# ttab.net
KiCad netlist of a schematic drawn in EAGLE
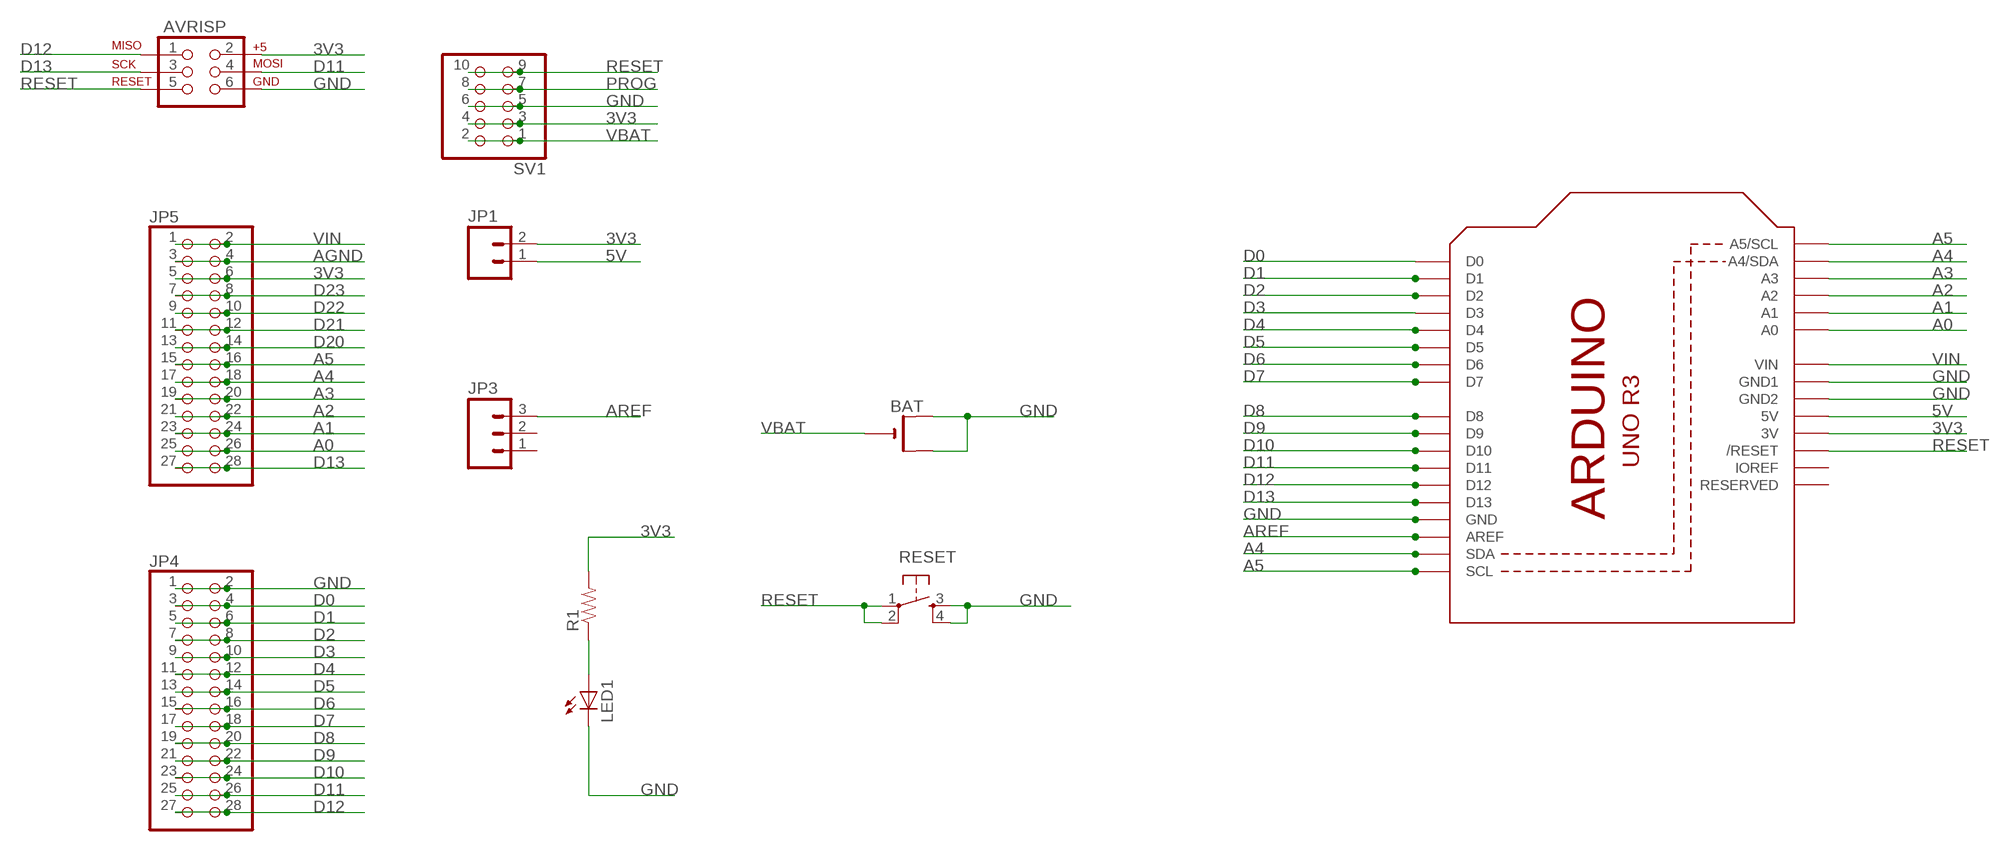
[diagram p0: schematic, sheet 1]

(export (version "E")
  (design (tool "Eeschema 10.0.6"))
  (components
    (comp (ref "AVRISP")
      (value "AVR_SPI_PRG_6PTH")
      (footprint "eagle-import:2X3")
      (libsource (lib "eagle-import") (part "AVR_SPI_PRG_6PTH"))
    )
    (comp (ref "BAT")
      (value "CR1220THM")
      (footprint "eagle-import:CR1220-THM")
      (libsource (lib "eagle-import") (part "CR1220THM"))
    )
    (comp (ref "JP1")
      (value "M02LOCK")
      (footprint "eagle-import:1X02_LOCK")
      (libsource (lib "eagle-import") (part "M02LOCK"))
    )
    (comp (ref "JP3")
      (value "M03PTH")
      (footprint "eagle-import:1X03")
      (libsource (lib "eagle-import") (part "M03PTH"))
    )
    (comp (ref "JP4")
      (value "PINHD-2X14")
      (footprint "eagle-import:2X14")
      (libsource (lib "eagle-import") (part "PINHD-2X14"))
    )
    (comp (ref "JP5")
      (value "PINHD-2X14")
      (footprint "eagle-import:2X14")
      (libsource (lib "eagle-import") (part "PINHD-2X14"))
    )
    (comp (ref "LED1")
      (value "LEDCHIP-LED0805")
      (footprint "eagle-import:CHIP-LED0805")
      (libsource (lib "eagle-import") (part "LEDCHIP-LED0805"))
    )
    (comp (ref "R1")
      (value "RESISTOR0805-RES")
      (footprint "eagle-import:0805")
      (libsource (lib "eagle-import") (part "RESISTOR0805-RES"))
    )
    (comp (ref "RESET")
      (value "TAC_SWITCHPTH")
      (footprint "eagle-import:TACTILE-PTH")
      (libsource (lib "eagle-import") (part "TAC_SWITCHPTH"))
    )
    (comp (ref "SV1")
      (value "PINHD-2X5")
      (footprint "eagle-import:2X05")
      (libsource (lib "eagle-import") (part "PINHD-2X5"))
    )
    (comp (ref "U4")
      (value "ARDUINOR3-DIMENSION")
      (footprint "eagle-import:ARDUINOR3")
      (libsource (lib "eagle-import") (part "ARDUINOR3-DIMENSION"))
    )
  )
  (nets
    (net (code "1") (name "/3V3") (class "Default")
      (node (ref "AVRISP") (pin "2") (pinfunction "2_2") (pintype "passive"))
      (node (ref "JP1") (pin "2") (pinfunction "2_2") (pintype "passive"))
      (node (ref "JP5") (pin "5") (pinfunction "5_5") (pintype "passive"))
      (node (ref "JP5") (pin "6") (pinfunction "6_6") (pintype "passive"))
      (node (ref "R1") (pin "2") (pinfunction "2_2") (pintype "passive"))
      (node (ref "SV1") (pin "3") (pinfunction "3_3") (pintype "passive"))
      (node (ref "SV1") (pin "4") (pinfunction "4_4") (pintype "passive"))
      (node (ref "U4") (pin "3V") (pinfunction "3V_3V") (pintype "power_in"))
    )
    (net (code "2") (name "/5V") (class "Default")
      (node (ref "JP1") (pin "1") (pinfunction "1_1") (pintype "passive"))
      (node (ref "U4") (pin "5V") (pinfunction "5V_5V") (pintype "power_in"))
    )
    (net (code "3") (name "/A0") (class "Default")
      (node (ref "JP5") (pin "25") (pinfunction "25_25") (pintype "passive"))
      (node (ref "JP5") (pin "26") (pinfunction "26_26") (pintype "passive"))
      (node (ref "U4") (pin "A0") (pinfunction "A0_A0") (pintype "bidirectional"))
    )
    (net (code "4") (name "/A1") (class "Default")
      (node (ref "JP5") (pin "23") (pinfunction "23_23") (pintype "passive"))
      (node (ref "JP5") (pin "24") (pinfunction "24_24") (pintype "passive"))
      (node (ref "U4") (pin "A1") (pinfunction "A1_A1") (pintype "bidirectional"))
    )
    (net (code "5") (name "/A2") (class "Default")
      (node (ref "JP5") (pin "21") (pinfunction "21_21") (pintype "passive"))
      (node (ref "JP5") (pin "22") (pinfunction "22_22") (pintype "passive"))
      (node (ref "U4") (pin "A2") (pinfunction "A2_A2") (pintype "bidirectional"))
    )
    (net (code "6") (name "/A3") (class "Default")
      (node (ref "JP5") (pin "19") (pinfunction "19_19") (pintype "passive"))
      (node (ref "JP5") (pin "20") (pinfunction "20_20") (pintype "passive"))
      (node (ref "U4") (pin "A3") (pinfunction "A3_A3") (pintype "bidirectional"))
    )
    (net (code "7") (name "/A4") (class "Default")
      (node (ref "JP5") (pin "17") (pinfunction "17_17") (pintype "passive"))
      (node (ref "JP5") (pin "18") (pinfunction "18_18") (pintype "passive"))
      (node (ref "U4") (pin "A4") (pinfunction "A4/SDA_A4") (pintype "bidirectional"))
      (node (ref "U4") (pin "SDA") (pinfunction "SDA_SDA") (pintype "bidirectional"))
    )
    (net (code "8") (name "/A5") (class "Default")
      (node (ref "JP5") (pin "15") (pinfunction "15_15") (pintype "passive"))
      (node (ref "JP5") (pin "16") (pinfunction "16_16") (pintype "passive"))
      (node (ref "U4") (pin "A5") (pinfunction "A5/SCL_A5") (pintype "bidirectional"))
      (node (ref "U4") (pin "SCL") (pinfunction "SCL_SCL") (pintype "bidirectional"))
    )
    (net (code "9") (name "/AGND") (class "Default")
      (node (ref "JP5") (pin "3") (pinfunction "3_3") (pintype "passive"))
      (node (ref "JP5") (pin "4") (pinfunction "4_4") (pintype "passive"))
    )
    (net (code "10") (name "/AREF") (class "Default")
      (node (ref "JP3") (pin "3") (pinfunction "3_3") (pintype "passive"))
      (node (ref "U4") (pin "AREF") (pinfunction "AREF_AREF") (pintype "bidirectional"))
    )
    (net (code "11") (name "/D0") (class "Default")
      (node (ref "JP4") (pin "3") (pinfunction "3_3") (pintype "passive"))
      (node (ref "JP4") (pin "4") (pinfunction "4_4") (pintype "passive"))
      (node (ref "U4") (pin "D0") (pinfunction "D0_D0") (pintype "bidirectional"))
    )
    (net (code "12") (name "/D1") (class "Default")
      (node (ref "JP4") (pin "5") (pinfunction "5_5") (pintype "passive"))
      (node (ref "JP4") (pin "6") (pinfunction "6_6") (pintype "passive"))
      (node (ref "U4") (pin "D1") (pinfunction "D1_D1") (pintype "bidirectional"))
    )
    (net (code "13") (name "/D2") (class "Default")
      (node (ref "JP4") (pin "7") (pinfunction "7_7") (pintype "passive"))
      (node (ref "JP4") (pin "8") (pinfunction "8_8") (pintype "passive"))
      (node (ref "U4") (pin "D2") (pinfunction "D2_D2") (pintype "bidirectional"))
    )
    (net (code "14") (name "/D3") (class "Default")
      (node (ref "JP4") (pin "10") (pinfunction "10_10") (pintype "passive"))
      (node (ref "JP4") (pin "9") (pinfunction "9_9") (pintype "passive"))
      (node (ref "U4") (pin "D3") (pinfunction "D3_D3") (pintype "bidirectional"))
    )
    (net (code "15") (name "/D4") (class "Default")
      (node (ref "JP4") (pin "11") (pinfunction "11_11") (pintype "passive"))
      (node (ref "JP4") (pin "12") (pinfunction "12_12") (pintype "passive"))
      (node (ref "U4") (pin "D4") (pinfunction "D4_D4") (pintype "bidirectional"))
    )
    (net (code "16") (name "/D5") (class "Default")
      (node (ref "JP4") (pin "13") (pinfunction "13_13") (pintype "passive"))
      (node (ref "JP4") (pin "14") (pinfunction "14_14") (pintype "passive"))
      (node (ref "U4") (pin "D5") (pinfunction "D5_D5") (pintype "bidirectional"))
    )
    (net (code "17") (name "/D6") (class "Default")
      (node (ref "JP4") (pin "15") (pinfunction "15_15") (pintype "passive"))
      (node (ref "JP4") (pin "16") (pinfunction "16_16") (pintype "passive"))
      (node (ref "U4") (pin "D6") (pinfunction "D6_D6") (pintype "bidirectional"))
    )
    (net (code "18") (name "/D7") (class "Default")
      (node (ref "JP4") (pin "17") (pinfunction "17_17") (pintype "passive"))
      (node (ref "JP4") (pin "18") (pinfunction "18_18") (pintype "passive"))
      (node (ref "U4") (pin "D7") (pinfunction "D7_D7") (pintype "bidirectional"))
    )
    (net (code "19") (name "/D8") (class "Default")
      (node (ref "JP4") (pin "19") (pinfunction "19_19") (pintype "passive"))
      (node (ref "JP4") (pin "20") (pinfunction "20_20") (pintype "passive"))
      (node (ref "U4") (pin "D8") (pinfunction "D8_D8") (pintype "bidirectional"))
    )
    (net (code "20") (name "/D9") (class "Default")
      (node (ref "JP4") (pin "21") (pinfunction "21_21") (pintype "passive"))
      (node (ref "JP4") (pin "22") (pinfunction "22_22") (pintype "passive"))
      (node (ref "U4") (pin "D9") (pinfunction "D9_D9") (pintype "bidirectional"))
    )
    (net (code "21") (name "/D10") (class "Default")
      (node (ref "JP4") (pin "23") (pinfunction "23_23") (pintype "passive"))
      (node (ref "JP4") (pin "24") (pinfunction "24_24") (pintype "passive"))
      (node (ref "U4") (pin "D10") (pinfunction "D10_D10") (pintype "bidirectional"))
    )
    (net (code "22") (name "/D11") (class "Default")
      (node (ref "AVRISP") (pin "4") (pinfunction "4_4") (pintype "passive"))
      (node (ref "JP4") (pin "25") (pinfunction "25_25") (pintype "passive"))
      (node (ref "JP4") (pin "26") (pinfunction "26_26") (pintype "passive"))
      (node (ref "U4") (pin "D11") (pinfunction "D11_D11") (pintype "bidirectional"))
    )
    (net (code "23") (name "/D12") (class "Default")
      (node (ref "AVRISP") (pin "1") (pinfunction "1_1") (pintype "passive"))
      (node (ref "JP4") (pin "27") (pinfunction "27_27") (pintype "passive"))
      (node (ref "JP4") (pin "28") (pinfunction "28_28") (pintype "passive"))
      (node (ref "U4") (pin "D12") (pinfunction "D12_D12") (pintype "bidirectional"))
    )
    (net (code "24") (name "/D13") (class "Default")
      (node (ref "AVRISP") (pin "3") (pinfunction "3_3") (pintype "passive"))
      (node (ref "JP5") (pin "27") (pinfunction "27_27") (pintype "passive"))
      (node (ref "JP5") (pin "28") (pinfunction "28_28") (pintype "passive"))
      (node (ref "U4") (pin "D13") (pinfunction "D13_D13") (pintype "bidirectional"))
    )
    (net (code "25") (name "/D20") (class "Default")
      (node (ref "JP5") (pin "13") (pinfunction "13_13") (pintype "passive"))
      (node (ref "JP5") (pin "14") (pinfunction "14_14") (pintype "passive"))
    )
    (net (code "26") (name "/D21") (class "Default")
      (node (ref "JP5") (pin "11") (pinfunction "11_11") (pintype "passive"))
      (node (ref "JP5") (pin "12") (pinfunction "12_12") (pintype "passive"))
    )
    (net (code "27") (name "/D22") (class "Default")
      (node (ref "JP5") (pin "10") (pinfunction "10_10") (pintype "passive"))
      (node (ref "JP5") (pin "9") (pinfunction "9_9") (pintype "passive"))
    )
    (net (code "28") (name "/D23") (class "Default")
      (node (ref "JP5") (pin "7") (pinfunction "7_7") (pintype "passive"))
      (node (ref "JP5") (pin "8") (pinfunction "8_8") (pintype "passive"))
    )
    (net (code "29") (name "/GND") (class "Default")
      (node (ref "AVRISP") (pin "6") (pinfunction "6_6") (pintype "passive"))
      (node (ref "BAT") (pin "+1") (pinfunction "+_+1") (pintype "passive"))
      (node (ref "BAT") (pin "+2") (pinfunction "+1_+2") (pintype "passive"))
      (node (ref "JP4") (pin "1") (pinfunction "1_1") (pintype "passive"))
      (node (ref "JP4") (pin "2") (pinfunction "2_2") (pintype "passive"))
      (node (ref "LED1") (pin "C") (pinfunction "C_C") (pintype "passive"))
      (node (ref "RESET") (pin "3") (pinfunction "3_3") (pintype "passive"))
      (node (ref "RESET") (pin "4") (pinfunction "4_4") (pintype "passive"))
      (node (ref "SV1") (pin "5") (pinfunction "5_5") (pintype "passive"))
      (node (ref "SV1") (pin "6") (pinfunction "6_6") (pintype "passive"))
      (node (ref "U4") (pin "GND") (pinfunction "GND_GND") (pintype "power_in"))
      (node (ref "U4") (pin "GND1") (pinfunction "GND1_GND1") (pintype "power_in"))
      (node (ref "U4") (pin "GND2") (pinfunction "GND2_GND2") (pintype "power_in"))
    )
    (net (code "30") (name "/PROG") (class "Default")
      (node (ref "SV1") (pin "7") (pinfunction "7_7") (pintype "passive"))
      (node (ref "SV1") (pin "8") (pinfunction "8_8") (pintype "passive"))
    )
    (net (code "31") (name "/RESET") (class "Default")
      (node (ref "AVRISP") (pin "5") (pinfunction "5_5") (pintype "passive"))
      (node (ref "RESET") (pin "1") (pinfunction "1_1") (pintype "passive"))
      (node (ref "RESET") (pin "2") (pinfunction "2_2") (pintype "passive"))
      (node (ref "SV1") (pin "10") (pinfunction "10_10") (pintype "passive"))
      (node (ref "SV1") (pin "9") (pinfunction "9_9") (pintype "passive"))
      (node (ref "U4") (pin "RESET") (pinfunction "/RESET_RESET") (pintype "bidirectional"))
    )
    (net (code "32") (name "/VBAT") (class "Default")
      (node (ref "BAT") (pin "-") (pinfunction "-_-") (pintype "passive"))
      (node (ref "SV1") (pin "1") (pinfunction "1_1") (pintype "passive"))
      (node (ref "SV1") (pin "2") (pinfunction "2_2") (pintype "passive"))
    )
    (net (code "33") (name "/VIN") (class "Default")
      (node (ref "JP5") (pin "1") (pinfunction "1_1") (pintype "passive"))
      (node (ref "JP5") (pin "2") (pinfunction "2_2") (pintype "passive"))
      (node (ref "U4") (pin "VIN") (pinfunction "VIN_VIN") (pintype "power_in"))
    )
    (net (code "34") (name "Net-(LED1-PadA)") (class "Default")
      (node (ref "LED1") (pin "A") (pinfunction "A_A") (pintype "passive"))
      (node (ref "R1") (pin "1") (pinfunction "1_1") (pintype "passive"))
    )
    (net (code "35") (name "unconnected-(JP3-Pad1)") (class "Default")
      (node (ref "JP3") (pin "1") (pinfunction "1_1") (pintype "passive"))
    )
    (net (code "36") (name "unconnected-(JP3-Pad2)") (class "Default")
      (node (ref "JP3") (pin "2") (pinfunction "2_2") (pintype "passive"))
    )
    (net (code "37") (name "unconnected-(U4-PadIOREF)") (class "Default")
      (node (ref "U4") (pin "IOREF") (pinfunction "IOREF_IOREF") (pintype "output"))
    )
    (net (code "38") (name "unconnected-(U4-PadRESERVED)") (class "Default")
      (node (ref "U4") (pin "RESERVED") (pinfunction "RESERVED_RESERVED") (pintype "no_connect"))
    )
  )
)
